# Led.net
KiCad netlist of a schematic drawn in Altium Designer
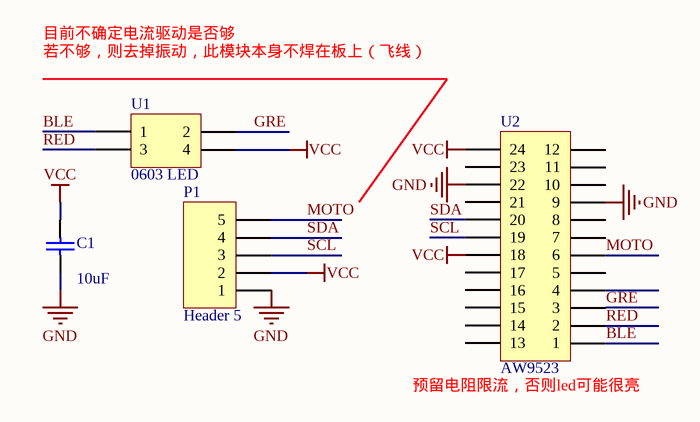
[diagram p0: Led.SchDoc]

(export (version "E")
  (design (tool "Eeschema 10.0.6"))
  (components
    (comp (ref "C1")
      (value "10uF")
      (footprint "1608[0603]")
      (description "Capacitor (Semiconductor SIM Model)")
      (fields (field (name "Comment") "Cap Semi") (field (name "PUBLISHER") "Altium Limited"))
      (libsource (lib "Miscellaneous Devices") (part "Cap Semi"))
    )
    (comp (ref "P1")
      (value "Header 5")
      (footprint "Pad_5")
      (description "Header, 5-Pin")
      (fields (field (name "PUBLISHER") "Altium Limited"))
      (libsource (lib "Miscellaneous Connectors") (part "Header 5"))
    )
    (comp (ref "U1")
      (value "0603 LED")
      (footprint "LED")
      (description "Header, 2-Pin, Dual row")
      (fields (field (name "PUBLISHER") "Altium Limited"))
      (libsource (lib "Miscellaneous Connectors") (part "Header 2X2"))
    )
    (comp (ref "U2")
      (value "AW9523")
      (footprint "AW9523")
      (description "Header, 12-Pin, Dual row")
      (fields (field (name "PUBLISHER") "Altium Limited"))
      (libsource (lib "Miscellaneous Connectors") (part "Header 12X2A"))
    )
  )
  (nets
    (net (code "1") (name "/BLE") (class "Default")
      (node (ref "U1") (pin "1") (pinfunction "1_1") (pintype "passive"))
      (node (ref "U2") (pin "1") (pinfunction "1_1") (pintype "passive"))
    )
    (net (code "2") (name "/GRE") (class "Default")
      (node (ref "U1") (pin "2") (pinfunction "2_2") (pintype "passive"))
      (node (ref "U2") (pin "3") (pinfunction "3_3") (pintype "passive"))
    )
    (net (code "3") (name "/MOTO") (class "Default")
      (node (ref "P1") (pin "5") (pinfunction "5_5") (pintype "passive"))
      (node (ref "U2") (pin "6") (pinfunction "6_6") (pintype "passive"))
    )
    (net (code "4") (name "/RED") (class "Default")
      (node (ref "U1") (pin "3") (pinfunction "3_3") (pintype "passive"))
      (node (ref "U2") (pin "2") (pinfunction "2_2") (pintype "passive"))
    )
    (net (code "5") (name "/SCL") (class "Default")
      (node (ref "P1") (pin "3") (pinfunction "3_3") (pintype "passive"))
      (node (ref "U2") (pin "19") (pinfunction "19_19") (pintype "passive"))
    )
    (net (code "6") (name "/SDA") (class "Default")
      (node (ref "P1") (pin "4") (pinfunction "4_4") (pintype "passive"))
      (node (ref "U2") (pin "20") (pinfunction "20_20") (pintype "passive"))
    )
    (net (code "7") (name "GND") (class "Default")
      (node (ref "C1") (pin "1") (pinfunction "1_1") (pintype "passive"))
      (node (ref "P1") (pin "1") (pinfunction "1_1") (pintype "passive"))
      (node (ref "U2") (pin "22") (pinfunction "22_22") (pintype "passive"))
      (node (ref "U2") (pin "9") (pinfunction "9_9") (pintype "passive"))
    )
    (net (code "8") (name "VCC") (class "Default")
      (node (ref "C1") (pin "2") (pinfunction "2_2") (pintype "passive"))
      (node (ref "P1") (pin "2") (pinfunction "2_2") (pintype "passive"))
      (node (ref "U1") (pin "4") (pinfunction "4_4") (pintype "passive"))
      (node (ref "U2") (pin "18") (pinfunction "18_18") (pintype "passive"))
      (node (ref "U2") (pin "24") (pinfunction "24_24") (pintype "passive"))
    )
    (net (code "9") (name "unconnected-(U2-Pad4)") (class "Default")
      (node (ref "U2") (pin "4") (pinfunction "4_4") (pintype "passive"))
    )
    (net (code "10") (name "unconnected-(U2-Pad5)") (class "Default")
      (node (ref "U2") (pin "5") (pinfunction "5_5") (pintype "passive"))
    )
    (net (code "11") (name "unconnected-(U2-Pad7)") (class "Default")
      (node (ref "U2") (pin "7") (pinfunction "7_7") (pintype "passive"))
    )
    (net (code "12") (name "unconnected-(U2-Pad8)") (class "Default")
      (node (ref "U2") (pin "8") (pinfunction "8_8") (pintype "passive"))
    )
    (net (code "13") (name "unconnected-(U2-Pad10)") (class "Default")
      (node (ref "U2") (pin "10") (pinfunction "10_10") (pintype "passive"))
    )
    (net (code "14") (name "unconnected-(U2-Pad11)") (class "Default")
      (node (ref "U2") (pin "11") (pinfunction "11_11") (pintype "passive"))
    )
    (net (code "15") (name "unconnected-(U2-Pad12)") (class "Default")
      (node (ref "U2") (pin "12") (pinfunction "12_12") (pintype "passive"))
    )
    (net (code "16") (name "unconnected-(U2-Pad13)") (class "Default")
      (node (ref "U2") (pin "13") (pinfunction "13_13") (pintype "passive"))
    )
    (net (code "17") (name "unconnected-(U2-Pad14)") (class "Default")
      (node (ref "U2") (pin "14") (pinfunction "14_14") (pintype "passive"))
    )
    (net (code "18") (name "unconnected-(U2-Pad15)") (class "Default")
      (node (ref "U2") (pin "15") (pinfunction "15_15") (pintype "passive"))
    )
    (net (code "19") (name "unconnected-(U2-Pad16)") (class "Default")
      (node (ref "U2") (pin "16") (pinfunction "16_16") (pintype "passive"))
    )
    (net (code "20") (name "unconnected-(U2-Pad17)") (class "Default")
      (node (ref "U2") (pin "17") (pinfunction "17_17") (pintype "passive"))
    )
    (net (code "21") (name "unconnected-(U2-Pad21)") (class "Default")
      (node (ref "U2") (pin "21") (pinfunction "21_21") (pintype "passive"))
    )
    (net (code "22") (name "unconnected-(U2-Pad23)") (class "Default")
      (node (ref "U2") (pin "23") (pinfunction "23_23") (pintype "passive"))
    )
  )
)
